# USB_Isolator.net
KiCad netlist of a schematic drawn in EAGLE
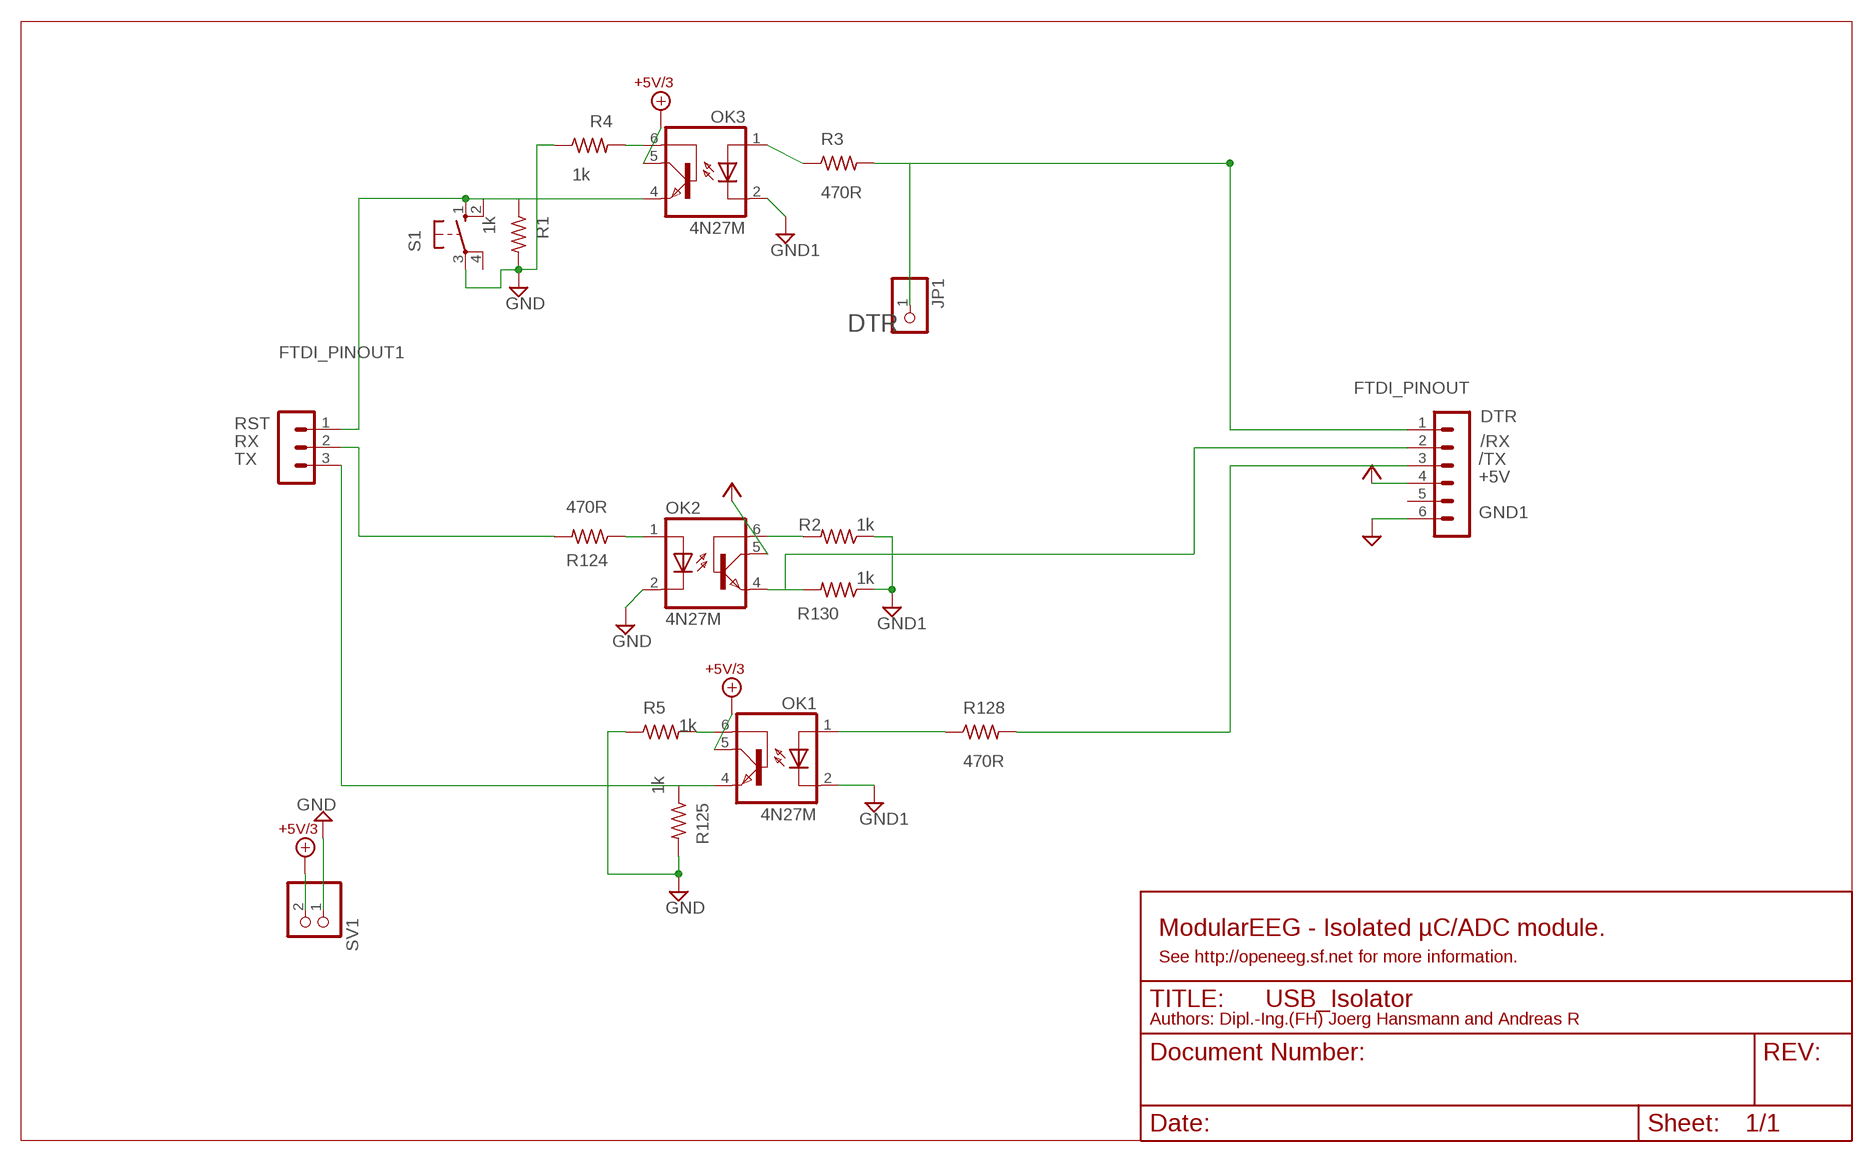
[diagram p0: schematic, sheet 1]

(export (version "E")
  (design (tool "Eeschema 10.0.6"))
  (components
    (comp (ref "FTDI_PINOUT")
      (value "MA06-1")
      (footprint "eagle-import:MA06-1")
      (libsource (lib "eagle-import") (part "MA06-1"))
    )
    (comp (ref "FTDI_PINOUT1")
      (value "MA03-1")
      (footprint "eagle-import:MA03-1")
      (libsource (lib "eagle-import") (part "MA03-1"))
    )
    (comp (ref "JP1")
      (value "PINHD-1X1")
      (footprint "eagle-import:1X01")
      (libsource (lib "eagle-import") (part "PINHD-1X1"))
    )
    (comp (ref "OK1")
      (value "4N27M")
      (footprint "eagle-import:DIL06")
      (fields (field (name "MF") "FAIRCHILD SEMICONDUCTOR"))
      (libsource (lib "eagle-import") (part "4N?M27"))
    )
    (comp (ref "OK2")
      (value "4N27M")
      (footprint "eagle-import:DIL06")
      (fields (field (name "MF") "FAIRCHILD SEMICONDUCTOR"))
      (libsource (lib "eagle-import") (part "4N?M27"))
    )
    (comp (ref "OK3")
      (value "4N27M")
      (footprint "eagle-import:DIL06")
      (fields (field (name "MF") "FAIRCHILD SEMICONDUCTOR"))
      (libsource (lib "eagle-import") (part "4N?M27"))
    )
    (comp (ref "R1")
      (value "1k")
      (footprint "eagle-import:0204_5")
      (libsource (lib "eagle-import") (part "R-US_0204/5"))
    )
    (comp (ref "R2")
      (value "1k")
      (footprint "eagle-import:0204_7")
      (libsource (lib "eagle-import") (part "R-US_0204/7"))
    )
    (comp (ref "R3")
      (value "470R")
      (footprint "eagle-import:0204_7")
      (libsource (lib "eagle-import") (part "R-US_0204/7"))
    )
    (comp (ref "R4")
      (value "1k")
      (footprint "eagle-import:0204V")
      (libsource (lib "eagle-import") (part "R-US_0204/2V"))
    )
    (comp (ref "R5")
      (value "1k")
      (footprint "eagle-import:0204_5")
      (libsource (lib "eagle-import") (part "R-US_0204/5"))
    )
    (comp (ref "R124")
      (value "470R")
      (footprint "eagle-import:0204_7")
      (libsource (lib "eagle-import") (part "R-US_0204/7"))
    )
    (comp (ref "R125")
      (value "1k")
      (footprint "eagle-import:0204_5")
      (libsource (lib "eagle-import") (part "R-US_0204/5"))
    )
    (comp (ref "R128")
      (value "470R")
      (footprint "eagle-import:0204_7")
      (libsource (lib "eagle-import") (part "R-US_0204/7"))
    )
    (comp (ref "R130")
      (value "1k")
      (footprint "eagle-import:0204_7")
      (libsource (lib "eagle-import") (part "R-US_0204/7"))
    )
    (comp (ref "S1")
      (value "10-XX")
      (footprint "eagle-import:B3F-10XX")
      (fields (field (name "MPN") "B3F-1000"))
      (libsource (lib "eagle-import") (part "10-XX"))
    )
    (comp (ref "SV1")
      (value "PINHD-1X2")
      (footprint "eagle-import:1X02")
      (libsource (lib "eagle-import") (part "PINHD-1X2"))
    )
  )
  (nets
    (net (code "1") (name "+5V") (class "Default")
      (node (ref "FTDI_PINOUT") (pin "4") (pinfunction "4_4") (pintype "passive"))
      (node (ref "OK2") (pin "5") (pinfunction "COL_5") (pintype "passive"))
    )
    (net (code "2") (name "+5V{slash}3") (class "Default")
      (node (ref "OK1") (pin "5") (pinfunction "COL_5") (pintype "passive"))
      (node (ref "OK3") (pin "5") (pinfunction "COL_5") (pintype "passive"))
      (node (ref "SV1") (pin "2") (pinfunction "2_2") (pintype "passive"))
    )
    (net (code "3") (name "/DTR") (class "Default")
      (node (ref "FTDI_PINOUT") (pin "1") (pinfunction "1_1") (pintype "passive"))
      (node (ref "JP1") (pin "1") (pinfunction "1_1") (pintype "passive"))
      (node (ref "R3") (pin "2") (pinfunction "2_2") (pintype "passive"))
    )
    (net (code "4") (name "/RST") (class "Default")
      (node (ref "FTDI_PINOUT1") (pin "1") (pinfunction "1_1") (pintype "passive"))
      (node (ref "OK3") (pin "4") (pinfunction "EMI_4") (pintype "passive"))
      (node (ref "R1") (pin "1") (pinfunction "1_1") (pintype "passive"))
      (node (ref "S1") (pin "1") (pinfunction "S_1") (pintype "passive"))
      (node (ref "S1") (pin "2") (pinfunction "S1_2") (pintype "passive"))
    )
    (net (code "5") (name "/RX") (class "Default")
      (node (ref "FTDI_PINOUT1") (pin "2") (pinfunction "2_2") (pintype "passive"))
      (node (ref "R124") (pin "2") (pinfunction "2_2") (pintype "passive"))
    )
    (net (code "6") (name "/TX") (class "Default")
      (node (ref "FTDI_PINOUT1") (pin "3") (pinfunction "3_3") (pintype "passive"))
      (node (ref "OK1") (pin "4") (pinfunction "EMI_4") (pintype "passive"))
      (node (ref "R125") (pin "1") (pinfunction "1_1") (pintype "passive"))
    )
    (net (code "7") (name "/{slash}RX") (class "Default")
      (node (ref "FTDI_PINOUT") (pin "2") (pinfunction "2_2") (pintype "passive"))
      (node (ref "OK2") (pin "4") (pinfunction "EMI_4") (pintype "passive"))
      (node (ref "R130") (pin "2") (pinfunction "2_2") (pintype "passive"))
    )
    (net (code "8") (name "/{slash}TX") (class "Default")
      (node (ref "FTDI_PINOUT") (pin "3") (pinfunction "3_3") (pintype "passive"))
      (node (ref "R128") (pin "2") (pinfunction "2_2") (pintype "passive"))
    )
    (net (code "9") (name "GND") (class "Default")
      (node (ref "OK2") (pin "2") (pinfunction "C_2") (pintype "passive"))
      (node (ref "R1") (pin "2") (pinfunction "2_2") (pintype "passive"))
      (node (ref "R125") (pin "2") (pinfunction "2_2") (pintype "passive"))
      (node (ref "R4") (pin "1") (pinfunction "1_1") (pintype "passive"))
      (node (ref "R5") (pin "1") (pinfunction "1_1") (pintype "passive"))
      (node (ref "S1") (pin "3") (pinfunction "P_3") (pintype "passive"))
      (node (ref "SV1") (pin "1") (pinfunction "1_1") (pintype "passive"))
    )
    (net (code "10") (name "GND1") (class "Default")
      (node (ref "FTDI_PINOUT") (pin "6") (pinfunction "6_6") (pintype "passive"))
      (node (ref "OK1") (pin "2") (pinfunction "C_2") (pintype "passive"))
      (node (ref "OK3") (pin "2") (pinfunction "C_2") (pintype "passive"))
      (node (ref "R130") (pin "1") (pinfunction "1_1") (pintype "passive"))
      (node (ref "R2") (pin "1") (pinfunction "1_1") (pintype "passive"))
    )
    (net (code "11") (name "Net-(OK1-A)") (class "Default")
      (node (ref "OK1") (pin "1") (pinfunction "A_1") (pintype "passive"))
      (node (ref "R128") (pin "1") (pinfunction "1_1") (pintype "passive"))
    )
    (net (code "12") (name "Net-(OK1-BAS)") (class "Default")
      (node (ref "OK1") (pin "6") (pinfunction "BAS_6") (pintype "passive"))
      (node (ref "R5") (pin "2") (pinfunction "2_2") (pintype "passive"))
    )
    (net (code "13") (name "Net-(OK2-A)") (class "Default")
      (node (ref "OK2") (pin "1") (pinfunction "A_1") (pintype "passive"))
      (node (ref "R124") (pin "1") (pinfunction "1_1") (pintype "passive"))
    )
    (net (code "14") (name "Net-(OK2-BAS)") (class "Default")
      (node (ref "OK2") (pin "6") (pinfunction "BAS_6") (pintype "passive"))
      (node (ref "R2") (pin "2") (pinfunction "2_2") (pintype "passive"))
    )
    (net (code "15") (name "Net-(OK3-A)") (class "Default")
      (node (ref "OK3") (pin "1") (pinfunction "A_1") (pintype "passive"))
      (node (ref "R3") (pin "1") (pinfunction "1_1") (pintype "passive"))
    )
    (net (code "16") (name "Net-(OK3-BAS)") (class "Default")
      (node (ref "OK3") (pin "6") (pinfunction "BAS_6") (pintype "passive"))
      (node (ref "R4") (pin "2") (pinfunction "2_2") (pintype "passive"))
    )
    (net (code "17") (name "unconnected-(FTDI_PINOUT-Pad5)") (class "Default")
      (node (ref "FTDI_PINOUT") (pin "5") (pinfunction "5_5") (pintype "passive"))
    )
    (net (code "18") (name "unconnected-(S1-P1-Pad4)") (class "Default")
      (node (ref "S1") (pin "4") (pinfunction "P1_4") (pintype "passive"))
    )
  )
)
